# USB.net
KiCad netlist of a schematic drawn in Altium Designer
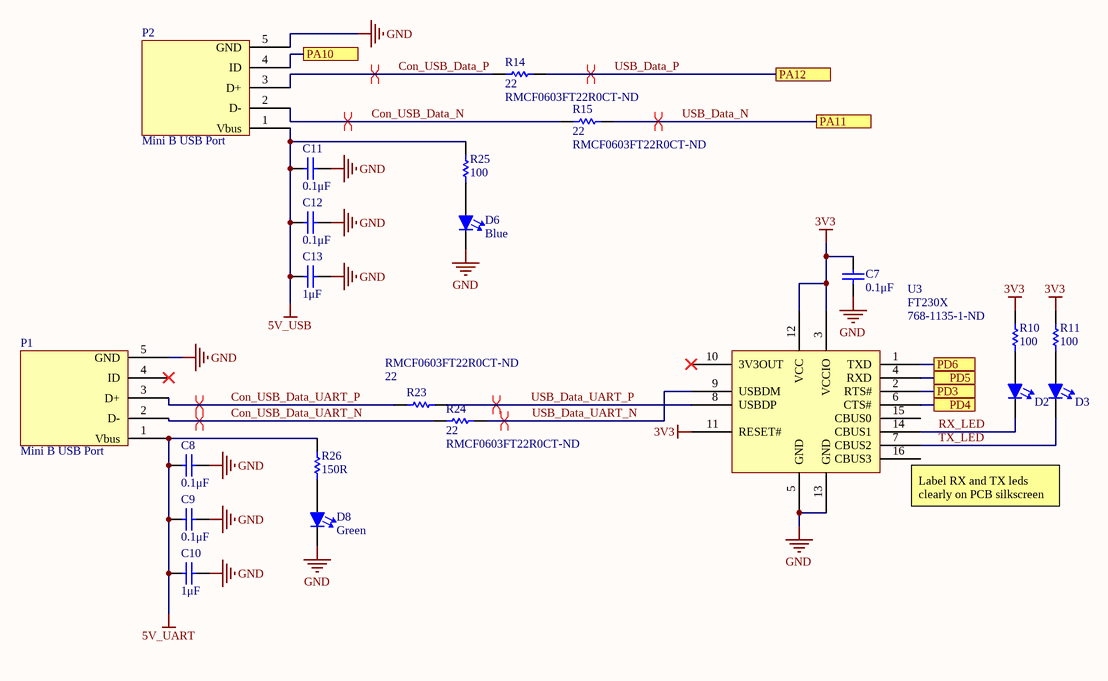
[diagram p0: USB.SchDoc]

(export (version "E")
  (design (tool "Eeschema 10.0.6"))
  (components
    (comp (ref "C7")
      (value "0.1μF")
      (footprint "CAPC1608N(0603\")")
      (description "Capacitor, Ceramic, 100V, +/- 10%, 0603 SMD, X7R")
      (fields
        (field (name "MFG") "TDK")
        (field (name "PUBLISHER") "AUVic")
        (field (name "CREATED BY") "Ashwin Sira")
      )
      (libsource (lib "AUVic_Integrated_Library_Capacitors") (part "0.1uF 100V 0603 SMD, Ceramic"))
    )
    (comp (ref "C8")
      (value "0.1μF")
      (footprint "CAPC1608N(0603\")")
      (description "Capacitor, Ceramic, 100V, +/- 10%, 0603 SMD, X7R")
      (fields
        (field (name "MFG") "TDK")
        (field (name "PUBLISHER") "AUVic")
        (field (name "CREATED BY") "Ashwin Sira")
      )
      (libsource (lib "AUVic_Integrated_Library_Capacitors") (part "0.1uF 100V 0603 SMD, Ceramic"))
    )
    (comp (ref "C9")
      (value "0.1μF")
      (footprint "CAPC1608N(0603\")")
      (description "Capacitor, Ceramic, 100V, +/- 10%, 0603 SMD, X7R")
      (fields
        (field (name "MFG") "TDK")
        (field (name "PUBLISHER") "AUVic")
        (field (name "CREATED BY") "Ashwin Sira")
      )
      (libsource (lib "AUVic_Integrated_Library_Capacitors") (part "0.1uF 100V 0603 SMD, Ceramic"))
    )
    (comp (ref "C10")
      (value "1μF")
      (footprint "CAPC1608N(0603\")")
      (description "Capacitor, Ceramic, 25V, +/- 10%, 0603 SMD, X5R")
      (fields
        (field (name "MFG") "Murata-Electronics-North-America")
        (field (name "PUBLISHER") "AUVic")
        (field (name "CREATED BY") "Andy Bates")
      )
      (libsource (lib "AUVic_Integrated_Library_Capacitors") (part "1uF 25V 0603 SMD, Ceramic"))
    )
    (comp (ref "C11")
      (value "0.1μF")
      (footprint "CAPC1608N(0603\")")
      (description "Capacitor, Ceramic, 100V, +/- 10%, 0603 SMD, X7R")
      (fields
        (field (name "MFG") "TDK")
        (field (name "PUBLISHER") "AUVic")
        (field (name "CREATED BY") "Ashwin Sira")
      )
      (libsource (lib "AUVic_Integrated_Library_Capacitors") (part "0.1uF 100V 0603 SMD, Ceramic"))
    )
    (comp (ref "C12")
      (value "0.1μF")
      (footprint "CAPC1608N(0603\")")
      (description "Capacitor, Ceramic, 100V, +/- 10%, 0603 SMD, X7R")
      (fields
        (field (name "MFG") "TDK")
        (field (name "PUBLISHER") "AUVic")
        (field (name "CREATED BY") "Ashwin Sira")
      )
      (libsource (lib "AUVic_Integrated_Library_Capacitors") (part "0.1uF 100V 0603 SMD, Ceramic"))
    )
    (comp (ref "C13")
      (value "1μF")
      (footprint "CAPC1608N(0603\")")
      (description "Capacitor, Ceramic, 25V, +/- 10%, 0603 SMD, X5R")
      (fields
        (field (name "MFG") "Murata-Electronics-North-America")
        (field (name "PUBLISHER") "AUVic")
        (field (name "CREATED BY") "Andy Bates")
      )
      (libsource (lib "AUVic_Integrated_Library_Capacitors") (part "1uF 25V 0603 SMD, Ceramic"))
    )
    (comp (ref "D2")
      (value "Red")
      (footprint "LED0805")
      (description "LED, 0805 (2012), Red, Clear")
      (fields (field (name "CREATED BY") "Ashwin Sira"))
      (libsource (lib "AUVic_Integrated_Library_Diodes") (part "LED, 0805 (2012), Red, Clear"))
    )
    (comp (ref "D3")
      (value "Red")
      (footprint "LED0805")
      (description "LED, 0805 (2012), Red, Clear")
      (fields (field (name "CREATED BY") "Ashwin Sira"))
      (libsource (lib "AUVic_Integrated_Library_Diodes") (part "LED, 0805 (2012), Red, Clear"))
    )
    (comp (ref "D6")
      (value "Blue")
      (footprint "LED0805")
      (description "LED, 0805 (2012), Blue, Clear")
      (fields (field (name "CREATED BY") "Ashwin Sira"))
      (libsource (lib "AUVic_Integrated_Library_Diodes") (part "LED, 0805 (2012), Blue, Clear"))
    )
    (comp (ref "D8")
      (value "Green")
      (footprint "LED0805")
      (description "LED, 0805 (2012), Green, Clear")
      (fields (field (name "CREATED BY") "Andy Bates"))
      (libsource (lib "AUVic_Integrated_Library_Diodes") (part "LED, 0805 (2012), Green, Clear"))
    )
    (comp (ref "P1")
      (value "Mini B USB Port")
      (footprint "Mini B USB Footprint")
      (description "Mini B USB Port - Female")
      (fields (field (name "CREATED BY") "Gabriel Green"))
      (libsource (lib "AUVic_Integrated_Library_Connectors") (part "Mini B USB Port"))
    )
    (comp (ref "P2")
      (value "Mini B USB Port")
      (footprint "Mini B USB Footprint")
      (description "Mini B USB Port - Female")
      (fields (field (name "CREATED BY") "Gabriel Green"))
      (libsource (lib "AUVic_Integrated_Library_Connectors") (part "Mini B USB Port"))
    )
    (comp (ref "R10")
      (value "100")
      (footprint "RESC1608N(0603\")")
      (description "100R, 1%, 1/10W, 0603 SMD")
      (fields (field (name "MADE BY") "Andy Bates"))
      (libsource (lib "AUVic_Integrated_Library_Resistors") (part "100R, 1%, 1/10W, 0603 SMD"))
    )
    (comp (ref "R11")
      (value "100")
      (footprint "RESC1608N(0603\")")
      (description "100R, 1%, 1/10W, 0603 SMD")
      (fields (field (name "MADE BY") "Andy Bates"))
      (libsource (lib "AUVic_Integrated_Library_Resistors") (part "100R, 1%, 1/10W, 0603 SMD"))
    )
    (comp (ref "R14")
      (value "22")
      (footprint "RESC1608N(0603\")")
      (description "22 Ohm, 1%, 1/10W , 0603, SMD")
      (fields
        (field (name "SUPPLIER PART NUMBER 1") "RMCF0603FT22R0CT-ND")
        (field (name "CREATED BY") "Robert Keen")
        (field (name "PUBLISHER") "AUVic")
      )
      (libsource (lib "AUVic_Integrated_Library_Resistors") (part "22 Ohm, 1%, 1/10W , 0603, SMD"))
    )
    (comp (ref "R15")
      (value "22")
      (footprint "RESC1608N(0603\")")
      (description "22 Ohm, 1%, 1/10W , 0603, SMD")
      (fields
        (field (name "SUPPLIER PART NUMBER 1") "RMCF0603FT22R0CT-ND")
        (field (name "CREATED BY") "Robert Keen")
        (field (name "PUBLISHER") "AUVic")
      )
      (libsource (lib "AUVic_Integrated_Library_Resistors") (part "22 Ohm, 1%, 1/10W , 0603, SMD"))
    )
    (comp (ref "R23")
      (value "22")
      (footprint "RESC1608N(0603\")")
      (description "22 Ohm, 1%, 1/10W , 0603, SMD")
      (fields
        (field (name "SUPPLIER PART NUMBER 1") "RMCF0603FT22R0CT-ND")
        (field (name "CREATED BY") "Robert Keen")
        (field (name "PUBLISHER") "AUVic")
      )
      (libsource (lib "AUVic_Integrated_Library_Resistors") (part "22 Ohm, 1%, 1/10W , 0603, SMD"))
    )
    (comp (ref "R24")
      (value "22")
      (footprint "RESC1608N(0603\")")
      (description "22 Ohm, 1%, 1/10W , 0603, SMD")
      (fields
        (field (name "SUPPLIER PART NUMBER 1") "RMCF0603FT22R0CT-ND")
        (field (name "CREATED BY") "Robert Keen")
        (field (name "PUBLISHER") "AUVic")
      )
      (libsource (lib "AUVic_Integrated_Library_Resistors") (part "22 Ohm, 1%, 1/10W , 0603, SMD"))
    )
    (comp (ref "R25")
      (value "100")
      (footprint "RESC1608N(0603\")")
      (description "100R, 1%, 1/10W, 0603 SMD")
      (fields (field (name "MADE BY") "Andy Bates"))
      (libsource (lib "AUVic_Integrated_Library_Resistors") (part "100R, 1%, 1/10W, 0603 SMD"))
    )
    (comp (ref "R26")
      (value "150R")
      (footprint "RESC1608N(0603\")")
      (description "RES SMD 150 OHM 1% 1/10W 0603")
      (fields (field (name "CREATED BY") "Robert Keen") (field (name "PUBLISHER") "AUVic"))
      (libsource (lib "AUVic_Integrated_Library_Resistors") (part "150R, 1%, 1/10W, 0603, SMD"))
    )
    (comp (ref "U3")
      (value "FT230X")
      (footprint "SSOP16")
      (fields
        (field (name "SUPPLIER PART NUMBER 1") "768-1135-1-ND")
        (field (name "CREATED BY") "Gabriel Green")
      )
      (libsource (lib "AUVic_Integrated_Library_Interface") (part "FTDI - USB to UART"))
    )
  )
  (nets
    (net (code "1") (name "/Con_USB_Data_N") (class "Default")
      (node (ref "P2") (pin "2") (pinfunction "D-_2") (pintype "passive"))
      (node (ref "R15") (pin "1") (pinfunction "1_1") (pintype "passive"))
    )
    (net (code "2") (name "/Con_USB_Data_P") (class "Default")
      (node (ref "P2") (pin "3") (pinfunction "D+_3") (pintype "passive"))
      (node (ref "R14") (pin "1") (pinfunction "1_1") (pintype "passive"))
    )
    (net (code "3") (name "/Con_USB_Data_UART_N") (class "Default")
      (node (ref "P1") (pin "2") (pinfunction "D-_2") (pintype "passive"))
      (node (ref "R24") (pin "1") (pinfunction "1_1") (pintype "passive"))
    )
    (net (code "4") (name "/Con_USB_Data_UART_P") (class "Default")
      (node (ref "P1") (pin "3") (pinfunction "D+_3") (pintype "passive"))
      (node (ref "R23") (pin "1") (pinfunction "1_1") (pintype "passive"))
    )
    (net (code "5") (name "/PA10") (class "Default")
      (node (ref "P2") (pin "4") (pinfunction "ID_4") (pintype "passive"))
    )
    (net (code "6") (name "/PD3") (class "Default")
      (node (ref "U3") (pin "2") (pinfunction "RTS#_2") (pintype "passive"))
    )
    (net (code "7") (name "/PD4") (class "Default")
      (node (ref "U3") (pin "6") (pinfunction "CTS#_6") (pintype "passive"))
    )
    (net (code "8") (name "/PD5") (class "Default")
      (node (ref "U3") (pin "4") (pinfunction "RXD_4") (pintype "passive"))
    )
    (net (code "9") (name "/PD6") (class "Default")
      (node (ref "U3") (pin "1") (pinfunction "TXD_1") (pintype "passive"))
    )
    (net (code "10") (name "/RX_LED") (class "Default")
      (node (ref "D2") (pin "1") (pinfunction "Cathode_1") (pintype "passive"))
      (node (ref "U3") (pin "14") (pinfunction "CBUS1_14") (pintype "passive"))
    )
    (net (code "11") (name "/TX_LED") (class "Default")
      (node (ref "D3") (pin "1") (pinfunction "Cathode_1") (pintype "passive"))
      (node (ref "U3") (pin "7") (pinfunction "CBUS2_7") (pintype "passive"))
    )
    (net (code "12") (name "/USB_Data_N") (class "Default")
      (node (ref "R15") (pin "2") (pinfunction "2_2") (pintype "passive"))
    )
    (net (code "13") (name "/USB_Data_P") (class "Default")
      (node (ref "R14") (pin "2") (pinfunction "2_2") (pintype "passive"))
    )
    (net (code "14") (name "/USB_Data_UART_N") (class "Default")
      (node (ref "R24") (pin "2") (pinfunction "2_2") (pintype "passive"))
      (node (ref "U3") (pin "9") (pinfunction "USBDM_9") (pintype "passive"))
    )
    (net (code "15") (name "/USB_Data_UART_P") (class "Default")
      (node (ref "R23") (pin "2") (pinfunction "2_2") (pintype "passive"))
      (node (ref "U3") (pin "8") (pinfunction "USBDP_8") (pintype "passive"))
    )
    (net (code "16") (name "3V3") (class "Default")
      (node (ref "C7") (pin "2") (pinfunction "Cathode_2") (pintype "passive"))
      (node (ref "R10") (pin "2") (pinfunction "2_2") (pintype "passive"))
      (node (ref "R11") (pin "2") (pinfunction "2_2") (pintype "passive"))
      (node (ref "U3") (pin "11") (pinfunction "RESET#_11") (pintype "passive"))
      (node (ref "U3") (pin "12") (pinfunction "VCC_12") (pintype "passive"))
      (node (ref "U3") (pin "3") (pinfunction "VCCIO_3") (pintype "passive"))
    )
    (net (code "17") (name "5V_UART") (class "Default")
      (node (ref "C10") (pin "2") (pinfunction "Cathode_2") (pintype "passive"))
      (node (ref "C8") (pin "2") (pinfunction "Cathode_2") (pintype "passive"))
      (node (ref "C9") (pin "2") (pinfunction "Cathode_2") (pintype "passive"))
      (node (ref "P1") (pin "1") (pinfunction "Vbus_1") (pintype "passive"))
      (node (ref "R26") (pin "2") (pinfunction "2_2") (pintype "passive"))
    )
    (net (code "18") (name "5V_USB") (class "Default")
      (node (ref "C11") (pin "2") (pinfunction "Cathode_2") (pintype "passive"))
      (node (ref "C12") (pin "2") (pinfunction "Cathode_2") (pintype "passive"))
      (node (ref "C13") (pin "2") (pinfunction "Cathode_2") (pintype "passive"))
      (node (ref "P2") (pin "1") (pinfunction "Vbus_1") (pintype "passive"))
      (node (ref "R25") (pin "2") (pinfunction "2_2") (pintype "passive"))
    )
    (net (code "19") (name "GND") (class "Default")
      (node (ref "C10") (pin "1") (pinfunction "Anode_1") (pintype "passive"))
      (node (ref "C11") (pin "1") (pinfunction "Anode_1") (pintype "passive"))
      (node (ref "C12") (pin "1") (pinfunction "Anode_1") (pintype "passive"))
      (node (ref "C13") (pin "1") (pinfunction "Anode_1") (pintype "passive"))
      (node (ref "C7") (pin "1") (pinfunction "Anode_1") (pintype "passive"))
      (node (ref "C8") (pin "1") (pinfunction "Anode_1") (pintype "passive"))
      (node (ref "C9") (pin "1") (pinfunction "Anode_1") (pintype "passive"))
      (node (ref "D6") (pin "1") (pinfunction "Cathode_1") (pintype "passive"))
      (node (ref "D8") (pin "1") (pinfunction "Cathode_1") (pintype "passive"))
      (node (ref "P1") (pin "5") (pinfunction "GND_5") (pintype "passive"))
      (node (ref "P2") (pin "5") (pinfunction "GND_5") (pintype "passive"))
      (node (ref "U3") (pin "13") (pinfunction "GND_13") (pintype "passive"))
      (node (ref "U3") (pin "5") (pinfunction "GND_5") (pintype "passive"))
    )
    (net (code "20") (name "Net-(D2-Anode)") (class "Default")
      (node (ref "D2") (pin "2") (pinfunction "Anode_2") (pintype "passive"))
      (node (ref "R10") (pin "1") (pinfunction "1_1") (pintype "passive"))
    )
    (net (code "21") (name "Net-(D3-Anode)") (class "Default")
      (node (ref "D3") (pin "2") (pinfunction "Anode_2") (pintype "passive"))
      (node (ref "R11") (pin "1") (pinfunction "1_1") (pintype "passive"))
    )
    (net (code "22") (name "Net-(D6-Anode)") (class "Default")
      (node (ref "D6") (pin "2") (pinfunction "Anode_2") (pintype "passive"))
      (node (ref "R25") (pin "1") (pinfunction "1_1") (pintype "passive"))
    )
    (net (code "23") (name "Net-(D8-Anode)") (class "Default")
      (node (ref "D8") (pin "2") (pinfunction "Anode_2") (pintype "passive"))
      (node (ref "R26") (pin "1") (pinfunction "1_1") (pintype "passive"))
    )
    (net (code "24") (name "unconnected-(P1-ID-Pad4)") (class "Default")
      (node (ref "P1") (pin "4") (pinfunction "ID_4") (pintype "passive+no_connect"))
    )
    (net (code "25") (name "unconnected-(U3-3V3OUT-Pad10)") (class "Default")
      (node (ref "U3") (pin "10") (pinfunction "3V3OUT_10") (pintype "passive+no_connect"))
    )
    (net (code "26") (name "unconnected-(U3-CBUS0-Pad15)") (class "Default")
      (node (ref "U3") (pin "15") (pinfunction "CBUS0_15") (pintype "passive"))
    )
    (net (code "27") (name "unconnected-(U3-CBUS3-Pad16)") (class "Default")
      (node (ref "U3") (pin "16") (pinfunction "CBUS3_16") (pintype "passive"))
    )
  )
)
